# SCH_555-circuit_2025-03-12.net
KiCad netlist of a schematic drawn in EasyEDA
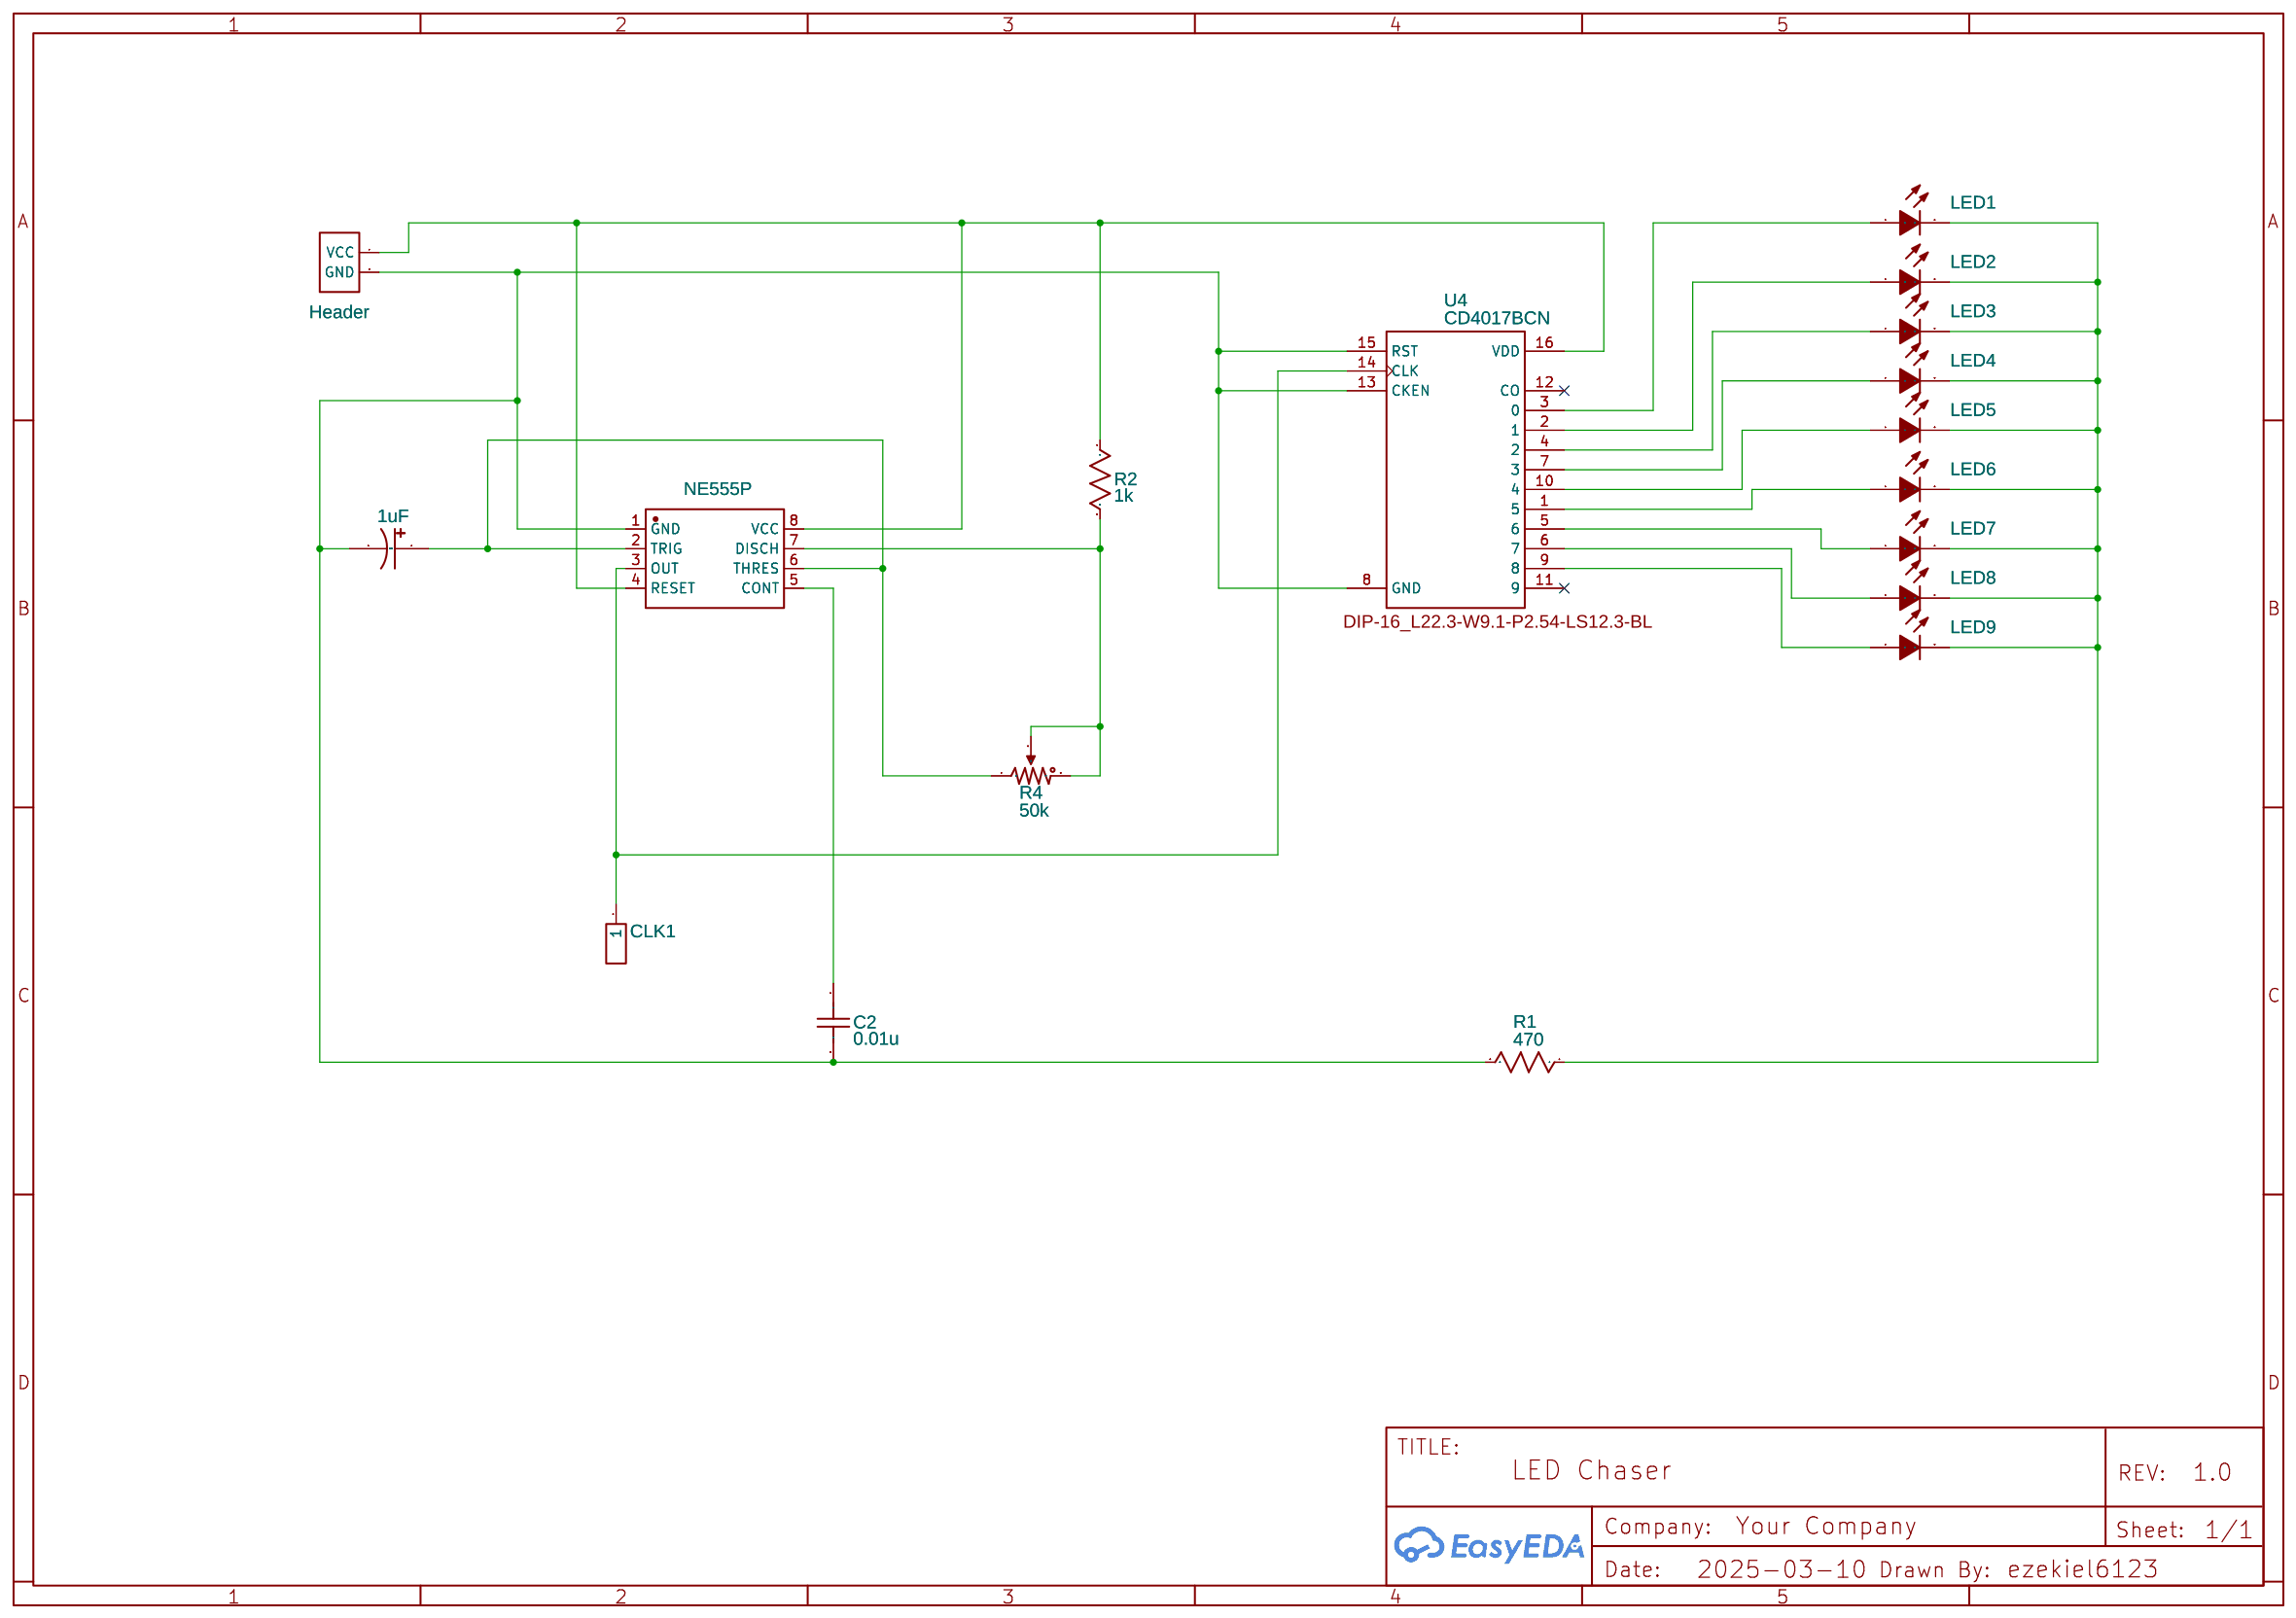
[diagram p0: schematic sheet]

(export (version "E")
  (design (tool "Eeschema 10.0.6"))
  (components
    (comp (ref "C1")
      (value "1uF")
      (fields (field (name "Manufacturer Part") "UVZ1H010MDD") (field (name "Manufacturer") "Nichicon(尼吉康)"))
      (libsource (lib "") (part "UVZ1H010MDD"))
    )
    (comp (ref "C2") (value "0.01u") (libsource (lib "") (part "C_0603_US")))
    (comp (ref "CLK1")
      (value "C81276")
      (fields
        (field (name "Manufacturer Part") "2.54-1*1P针")
        (field (name "Manufacturer") "BOOMELE(Boom Precision Elec)")
      )
      (libsource (lib "") (part "Header-Male-2.54_1x1"))
    )
    (comp (ref "H1") (value "Header") (libsource (lib "") (part "HEADER-FEMALE-2.54_1X2")))
    (comp (ref "LED1") (value "LED_5MM") (libsource (lib "") (part "LED_5MM")))
    (comp (ref "LED2") (value "LED_5MM") (libsource (lib "") (part "LED_5MM")))
    (comp (ref "LED3") (value "LED_5MM") (libsource (lib "") (part "LED_5MM")))
    (comp (ref "LED4") (value "LED_5MM") (libsource (lib "") (part "LED_5MM")))
    (comp (ref "LED5") (value "LED_5MM") (libsource (lib "") (part "LED_5MM")))
    (comp (ref "LED6") (value "LED_5MM") (libsource (lib "") (part "LED_5MM")))
    (comp (ref "LED7") (value "LED_5MM") (libsource (lib "") (part "LED_5MM")))
    (comp (ref "LED8") (value "LED_5MM") (libsource (lib "") (part "LED_5MM")))
    (comp (ref "LED9") (value "LED_5MM") (libsource (lib "") (part "LED_5MM")))
    (comp (ref "R1")
      (value "470")
      (fields (field (name "Manufacturer Part") "?"))
      (libsource (lib "") (part "Resistor_1"))
    )
    (comp (ref "R2")
      (value "1k")
      (fields (field (name "Manufacturer Part") "?"))
      (libsource (lib "") (part "Resistor"))
    )
    (comp (ref "R4")
      (value "50k")
      (fields (field (name "Manufacturer Part") "?"))
      (libsource (lib "") (part "Potentiometer"))
    )
    (comp (ref "U2")
      (value "NE555P")
      (fields (field (name "Manufacturer") "TI(德州仪器)"))
      (libsource (lib "") (part "NE555P"))
    )
    (comp (ref "U4") (value "CD4017BCN") (libsource (lib "") (part "CD4017BCN")))
  )
  (nets
    (net (code "1") (name "Net-(H1-GND)") (class "Default")
      (node (ref "C1") (pin "2") (pinfunction "2_2") (pintype "unspecified"))
      (node (ref "C2") (pin "2") (pinfunction "2_2") (pintype "unspecified"))
      (node (ref "H1") (pin "2") (pinfunction "GND_2") (pintype "unspecified"))
      (node (ref "R1") (pin "2") (pinfunction "2_2") (pintype "unspecified"))
      (node (ref "U2") (pin "1") (pinfunction "GND_1") (pintype "unspecified"))
      (node (ref "U4") (pin "13") (pinfunction "CKEN_13") (pintype "unspecified"))
      (node (ref "U4") (pin "15") (pinfunction "RST_15") (pintype "unspecified"))
      (node (ref "U4") (pin "8") (pinfunction "GND_8") (pintype "passive"))
    )
    (net (code "2") (name "Net-(H1-VCC)") (class "Default")
      (node (ref "H1") (pin "1") (pinfunction "VCC_1") (pintype "unspecified"))
      (node (ref "R2") (pin "1") (pinfunction "1_1") (pintype "unspecified"))
      (node (ref "U2") (pin "4") (pinfunction "RESET_4") (pintype "unspecified"))
      (node (ref "U2") (pin "8") (pinfunction "VCC_8") (pintype "unspecified"))
      (node (ref "U4") (pin "16") (pinfunction "VDD_16") (pintype "passive"))
    )
    (net (code "3") (name "Net-(LED1-A)") (class "Default")
      (node (ref "LED1") (pin "1") (pinfunction "A_1") (pintype "input"))
      (node (ref "U4") (pin "3") (pinfunction "0_3") (pintype "output"))
    )
    (net (code "4") (name "Net-(LED1-K)") (class "Default")
      (node (ref "LED1") (pin "2") (pinfunction "K_2") (pintype "input"))
      (node (ref "LED2") (pin "2") (pinfunction "K_2") (pintype "input"))
      (node (ref "LED3") (pin "2") (pinfunction "K_2") (pintype "input"))
      (node (ref "LED4") (pin "2") (pinfunction "K_2") (pintype "input"))
      (node (ref "LED5") (pin "2") (pinfunction "K_2") (pintype "input"))
      (node (ref "LED6") (pin "2") (pinfunction "K_2") (pintype "input"))
      (node (ref "LED7") (pin "2") (pinfunction "K_2") (pintype "input"))
      (node (ref "LED8") (pin "2") (pinfunction "K_2") (pintype "input"))
      (node (ref "LED9") (pin "2") (pinfunction "K_2") (pintype "input"))
      (node (ref "R1") (pin "1") (pinfunction "1_1") (pintype "unspecified"))
    )
    (net (code "5") (name "Net-(LED2-A)") (class "Default")
      (node (ref "LED2") (pin "1") (pinfunction "A_1") (pintype "input"))
      (node (ref "U4") (pin "2") (pinfunction "1_2") (pintype "output"))
    )
    (net (code "6") (name "Net-(LED3-A)") (class "Default")
      (node (ref "LED3") (pin "1") (pinfunction "A_1") (pintype "input"))
      (node (ref "U4") (pin "4") (pinfunction "2_4") (pintype "output"))
    )
    (net (code "7") (name "Net-(LED4-A)") (class "Default")
      (node (ref "LED4") (pin "1") (pinfunction "A_1") (pintype "input"))
      (node (ref "U4") (pin "7") (pinfunction "3_7") (pintype "output"))
    )
    (net (code "8") (name "Net-(LED5-A)") (class "Default")
      (node (ref "LED5") (pin "1") (pinfunction "A_1") (pintype "input"))
      (node (ref "U4") (pin "10") (pinfunction "4_10") (pintype "output"))
    )
    (net (code "9") (name "Net-(LED6-A)") (class "Default")
      (node (ref "LED6") (pin "1") (pinfunction "A_1") (pintype "input"))
      (node (ref "U4") (pin "1") (pinfunction "5_1") (pintype "output"))
    )
    (net (code "10") (name "Net-(LED7-A)") (class "Default")
      (node (ref "LED7") (pin "1") (pinfunction "A_1") (pintype "input"))
      (node (ref "U4") (pin "5") (pinfunction "6_5") (pintype "output"))
    )
    (net (code "11") (name "Net-(LED8-A)") (class "Default")
      (node (ref "LED8") (pin "1") (pinfunction "A_1") (pintype "input"))
      (node (ref "U4") (pin "6") (pinfunction "7_6") (pintype "output"))
    )
    (net (code "12") (name "Net-(LED9-A)") (class "Default")
      (node (ref "LED9") (pin "1") (pinfunction "A_1") (pintype "input"))
      (node (ref "U4") (pin "9") (pinfunction "8_9") (pintype "output"))
    )
    (net (code "13") (name "Net-(R4-2)") (class "Default")
      (node (ref "R2") (pin "2") (pinfunction "2_2") (pintype "unspecified"))
      (node (ref "R4") (pin "2") (pinfunction "3_2") (pintype "unspecified"))
      (node (ref "R4") (pin "3") (pinfunction "2_3") (pintype "unspecified"))
      (node (ref "U2") (pin "7") (pinfunction "DISCH_7") (pintype "unspecified"))
    )
    (net (code "14") (name "Net-(U2-CONT)") (class "Default")
      (node (ref "C2") (pin "1") (pinfunction "1_1") (pintype "unspecified"))
      (node (ref "U2") (pin "5") (pinfunction "CONT_5") (pintype "unspecified"))
    )
    (net (code "15") (name "Net-(U2-OUT)") (class "Default")
      (node (ref "CLK1") (pin "1") (pinfunction "1_1") (pintype "unspecified"))
      (node (ref "U2") (pin "3") (pinfunction "OUT_3") (pintype "unspecified"))
      (node (ref "U4") (pin "14") (pinfunction "CLK_14") (pintype "unspecified"))
    )
    (net (code "16") (name "Net-(U2-THRES)") (class "Default")
      (node (ref "C1") (pin "1") (pinfunction "1_1") (pintype "unspecified"))
      (node (ref "R4") (pin "1") (pinfunction "1_1") (pintype "unspecified"))
      (node (ref "U2") (pin "2") (pinfunction "TRIG_2") (pintype "unspecified"))
      (node (ref "U2") (pin "6") (pinfunction "THRES_6") (pintype "unspecified"))
    )
    (net (code "17") (name "unconnected-(U4-9-Pad11)") (class "Default")
      (node (ref "U4") (pin "11") (pinfunction "9_11") (pintype "output+no_connect"))
    )
    (net (code "18") (name "unconnected-(U4-CO-Pad12)") (class "Default")
      (node (ref "U4") (pin "12") (pinfunction "CO_12") (pintype "output+no_connect"))
    )
  )
)
